# Master.net
KiCad netlist of a schematic drawn in Altium Designer
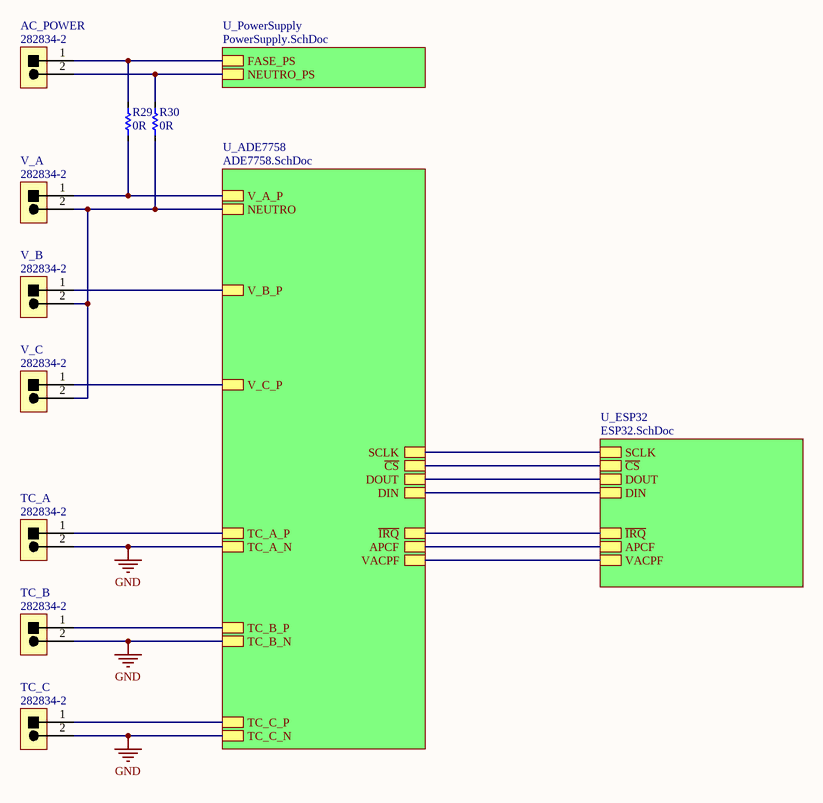
[diagram p0: Master.SchDoc]

(export (version "E")
  (design (tool "Eeschema 10.0.6"))
  (components
    (comp (ref "AC_POWER")
      (value "Conector")
      (footprint "TEC_282834-2")
      (description "TERM BLOCK 2POS SIDE ENT 2.54MM")
      (fields
        (field (name "PART NUMBER") "282834-2")
        (field (name "MANUFACTURER") "TE Connectivity AMP Connectors")
      )
      (libsource (lib "Simbolos") (part "Conector 2x1"))
    )
    (comp (ref "R29")
      (value "0R")
      (footprint "RES0603")
      (description "Resistor")
      (libsource (lib "Simbolos") (part "Resistor"))
    )
    (comp (ref "R30")
      (value "0R")
      (footprint "RES0603")
      (description "Resistor")
      (libsource (lib "Simbolos") (part "Resistor"))
    )
    (comp (ref "TC_A")
      (value "Conector")
      (footprint "TEC_282834-2")
      (description "TERM BLOCK 2POS SIDE ENT 2.54MM")
      (fields
        (field (name "PART NUMBER") "282834-2")
        (field (name "MANUFACTURER") "TE Connectivity AMP Connectors")
      )
      (libsource (lib "Simbolos") (part "Conector 2x1"))
    )
    (comp (ref "TC_B")
      (value "Conector")
      (footprint "TEC_282834-2")
      (description "TERM BLOCK 2POS SIDE ENT 2.54MM")
      (fields
        (field (name "PART NUMBER") "282834-2")
        (field (name "MANUFACTURER") "TE Connectivity AMP Connectors")
      )
      (libsource (lib "Simbolos") (part "Conector 2x1"))
    )
    (comp (ref "TC_C")
      (value "Conector")
      (footprint "TEC_282834-2")
      (description "TERM BLOCK 2POS SIDE ENT 2.54MM")
      (fields
        (field (name "PART NUMBER") "282834-2")
        (field (name "MANUFACTURER") "TE Connectivity AMP Connectors")
      )
      (libsource (lib "Simbolos") (part "Conector 2x1"))
    )
    (comp (ref "V_A")
      (value "Conector")
      (footprint "TEC_282834-2")
      (description "TERM BLOCK 2POS SIDE ENT 2.54MM")
      (fields
        (field (name "PART NUMBER") "282834-2")
        (field (name "MANUFACTURER") "TE Connectivity AMP Connectors")
      )
      (libsource (lib "Simbolos") (part "Conector 2x1"))
    )
    (comp (ref "V_B")
      (value "Conector")
      (footprint "TEC_282834-2")
      (description "TERM BLOCK 2POS SIDE ENT 2.54MM")
      (fields
        (field (name "PART NUMBER") "282834-2")
        (field (name "MANUFACTURER") "TE Connectivity AMP Connectors")
      )
      (libsource (lib "Simbolos") (part "Conector 2x1"))
    )
    (comp (ref "V_C")
      (value "Conector")
      (footprint "TEC_282834-2")
      (description "TERM BLOCK 2POS SIDE ENT 2.54MM")
      (fields
        (field (name "PART NUMBER") "282834-2")
        (field (name "MANUFACTURER") "TE Connectivity AMP Connectors")
      )
      (libsource (lib "Simbolos") (part "Conector 2x1"))
    )
  )
  (nets
    (net (code "4") (name "/FASE_PS") (class "Default")
      (node (ref "AC_POWER") (pin "1") (pinfunction "1_1") (pintype "passive"))
      (node (ref "R29") (pin "1") (pinfunction "1_1") (pintype "passive"))
    )
    (net (code "5") (name "/NEUTRO") (class "Default")
      (node (ref "R30") (pin "2") (pinfunction "2_2") (pintype "passive"))
      (node (ref "V_A") (pin "2") (pinfunction "2_2") (pintype "passive"))
      (node (ref "V_B") (pin "2") (pinfunction "2_2") (pintype "passive"))
      (node (ref "V_C") (pin "2") (pinfunction "2_2") (pintype "passive"))
    )
    (net (code "6") (name "/NEUTRO_PS") (class "Default")
      (node (ref "AC_POWER") (pin "2") (pinfunction "2_2") (pintype "passive"))
      (node (ref "R30") (pin "1") (pinfunction "1_1") (pintype "passive"))
    )
    (net (code "8") (name "/TC_A_P") (class "Default")
      (node (ref "TC_A") (pin "1") (pinfunction "1_1") (pintype "passive"))
    )
    (net (code "9") (name "/TC_B_P") (class "Default")
      (node (ref "TC_B") (pin "1") (pinfunction "1_1") (pintype "passive"))
    )
    (net (code "10") (name "/TC_C_P") (class "Default")
      (node (ref "TC_C") (pin "1") (pinfunction "1_1") (pintype "passive"))
    )
    (net (code "12") (name "/V_A_P") (class "Default")
      (node (ref "R29") (pin "2") (pinfunction "2_2") (pintype "passive"))
      (node (ref "V_A") (pin "1") (pinfunction "1_1") (pintype "passive"))
    )
    (net (code "13") (name "/V_B_P") (class "Default")
      (node (ref "V_B") (pin "1") (pinfunction "1_1") (pintype "passive"))
    )
    (net (code "14") (name "/V_C_P") (class "Default")
      (node (ref "V_C") (pin "1") (pinfunction "1_1") (pintype "passive"))
    )
    (net (code "17") (name "GND") (class "Default")
      (node (ref "TC_A") (pin "2") (pinfunction "2_2") (pintype "passive"))
      (node (ref "TC_B") (pin "2") (pinfunction "2_2") (pintype "passive"))
      (node (ref "TC_C") (pin "2") (pinfunction "2_2") (pintype "passive"))
    )
  )
)
